# OSO-MISC-21-022_Temperature_GPIO_I2C_Boa.net
KiCad netlist of a schematic drawn in EAGLE
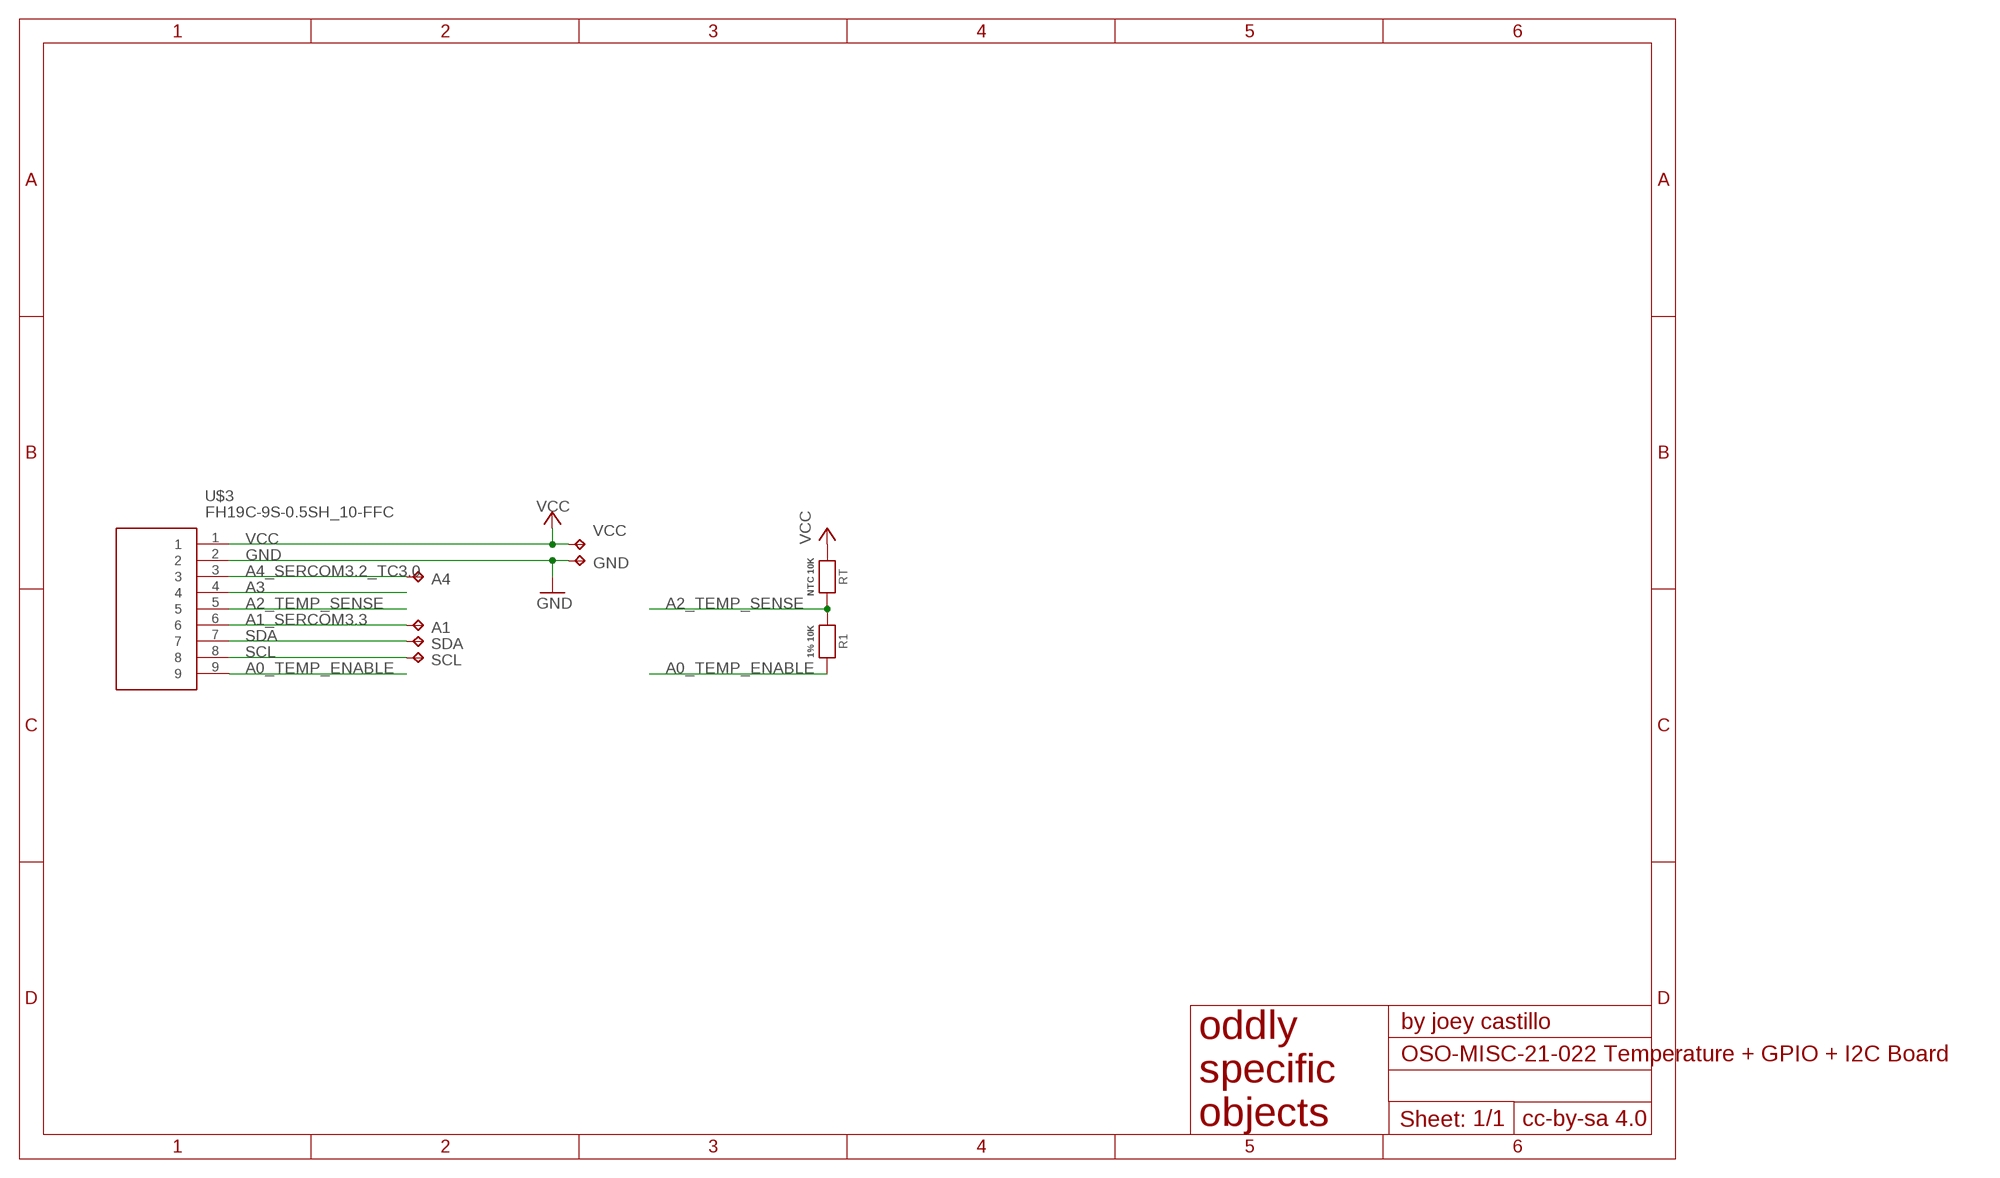
[diagram p0: schematic, sheet 1]

(export (version "E")
  (design (tool "Eeschema 10.0.6"))
  (components
    (comp (ref "A1")
      (value "TPB1,27")
      (footprint "eagle-import:B1,27")
      (libsource (lib "eagle-import") (part "TPB1,27"))
    )
    (comp (ref "A4")
      (value "TPB1,27")
      (footprint "eagle-import:B1,27")
      (libsource (lib "eagle-import") (part "TPB1,27"))
    )
    (comp (ref "GND")
      (value "TPB1,27")
      (footprint "eagle-import:B1,27")
      (libsource (lib "eagle-import") (part "TPB1,27"))
    )
    (comp (ref "R1")
      (value "1% 10K")
      (footprint "eagle-import:_0603MP")
      (libsource (lib "eagle-import") (part "RESISTOR_0603MP"))
    )
    (comp (ref "RT")
      (value "NTC 10K")
      (footprint "eagle-import:_0603MP")
      (libsource (lib "eagle-import") (part "RESISTOR_0603MP"))
    )
    (comp (ref "SCL")
      (value "TPB1,27")
      (footprint "eagle-import:B1,27")
      (libsource (lib "eagle-import") (part "TPB1,27"))
    )
    (comp (ref "SDA")
      (value "TPB1,27")
      (footprint "eagle-import:B1,27")
      (libsource (lib "eagle-import") (part "TPB1,27"))
    )
    (comp (ref "U$3")
      (value "FH19C-9S-0.5SH_10-FFC")
      (footprint "eagle-import:FH19C9S05SH10-FFC")
      (libsource (lib "eagle-import") (part "FH19C-9S-0.5SH_10-FFC"))
    )
    (comp (ref "VCC")
      (value "TPB1,27")
      (footprint "eagle-import:B1,27")
      (libsource (lib "eagle-import") (part "TPB1,27"))
    )
  )
  (nets
    (net (code "1") (name "/A0_TEMP_ENABLE") (class "Default")
      (node (ref "R1") (pin "2") (pinfunction "2_2") (pintype "passive"))
      (node (ref "U$3") (pin "9") (pinfunction "9_9") (pintype "bidirectional"))
    )
    (net (code "2") (name "/A1_SERCOM3.3") (class "Default")
      (node (ref "A1") (pin "TP") (pinfunction "TP_TP") (pintype "input"))
      (node (ref "U$3") (pin "6") (pinfunction "6_6") (pintype "bidirectional"))
    )
    (net (code "3") (name "/A2_TEMP_SENSE") (class "Default")
      (node (ref "R1") (pin "1") (pinfunction "1_1") (pintype "passive"))
      (node (ref "RT") (pin "2") (pinfunction "2_2") (pintype "passive"))
      (node (ref "U$3") (pin "5") (pinfunction "5_5") (pintype "bidirectional"))
    )
    (net (code "4") (name "/A3") (class "Default")
      (node (ref "U$3") (pin "4") (pinfunction "4_4") (pintype "bidirectional"))
    )
    (net (code "5") (name "/A4_SERCOM3.2_TC3.0") (class "Default")
      (node (ref "A4") (pin "TP") (pinfunction "TP_TP") (pintype "input"))
      (node (ref "U$3") (pin "3") (pinfunction "3_3") (pintype "bidirectional"))
    )
    (net (code "6") (name "/SCL") (class "Default")
      (node (ref "SCL") (pin "TP") (pinfunction "TP_TP") (pintype "input"))
      (node (ref "U$3") (pin "8") (pinfunction "8_8") (pintype "bidirectional"))
    )
    (net (code "7") (name "/SDA") (class "Default")
      (node (ref "SDA") (pin "TP") (pinfunction "TP_TP") (pintype "input"))
      (node (ref "U$3") (pin "7") (pinfunction "7_7") (pintype "bidirectional"))
    )
    (net (code "8") (name "GND") (class "Default")
      (node (ref "GND") (pin "TP") (pinfunction "TP_TP") (pintype "input"))
      (node (ref "U$3") (pin "2") (pinfunction "2_2") (pintype "bidirectional"))
    )
    (net (code "9") (name "VCC") (class "Default")
      (node (ref "RT") (pin "1") (pinfunction "1_1") (pintype "passive"))
      (node (ref "U$3") (pin "1") (pinfunction "1_1") (pintype "bidirectional"))
      (node (ref "VCC") (pin "TP") (pinfunction "TP_TP") (pintype "input"))
    )
  )
)
